# Board.net
KiCad netlist of a schematic drawn in EAGLE
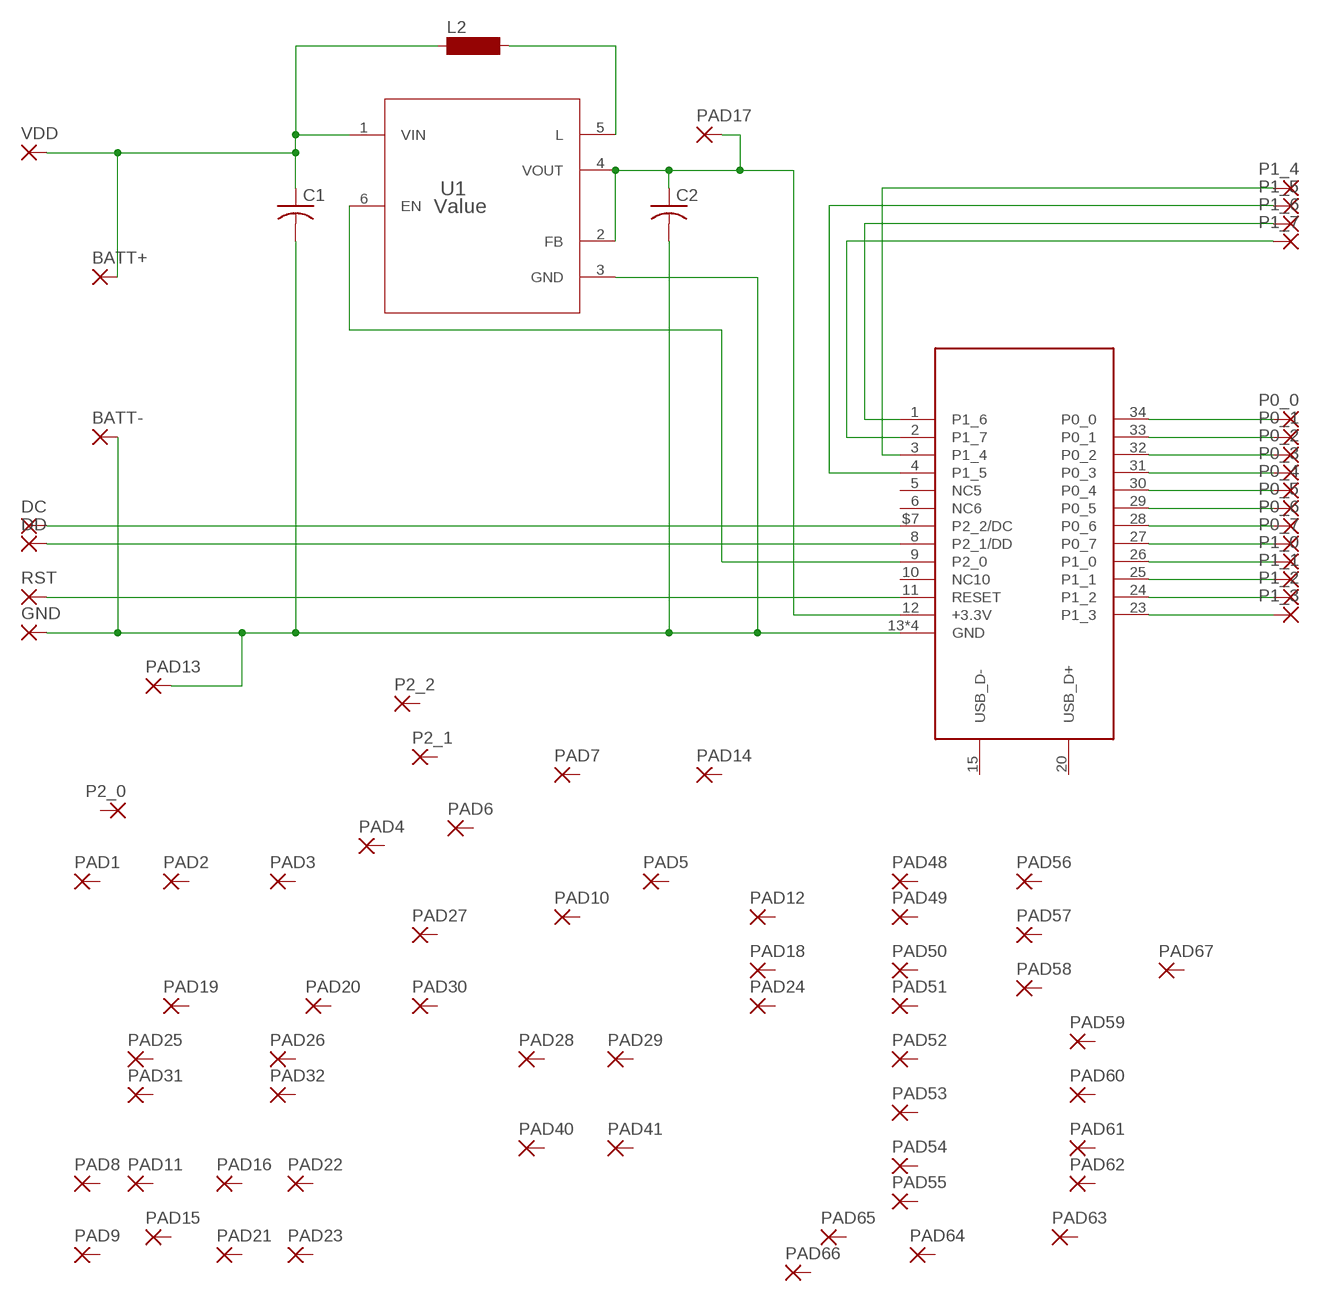
[diagram p0: schematic, sheet 1]

(export (version "E")
  (design (tool "Eeschema 10.0.6"))
  (components
    (comp (ref "BATT+")
      (value "1,6/0,9")
      (footprint "eagle-import:1,6_0,9")
      (libsource (lib "eagle-import") (part "1,6/0,9"))
    )
    (comp (ref "BATT-")
      (value "1,6/0,9")
      (footprint "eagle-import:1,6_0,9")
      (libsource (lib "eagle-import") (part "1,6/0,9"))
    )
    (comp (ref "C1")
      (value "C-USC0402")
      (footprint "eagle-import:C0402")
      (libsource (lib "eagle-import") (part "C-USC0402"))
    )
    (comp (ref "C2")
      (value "C-USC0402")
      (footprint "eagle-import:C0402")
      (libsource (lib "eagle-import") (part "C-USC0402"))
    )
    (comp (ref "DC")
      (value "SMD2")
      (footprint "eagle-import:SMD1,27-2,54")
      (libsource (lib "eagle-import") (part "SMD2"))
    )
    (comp (ref "DD")
      (value "SMD2")
      (footprint "eagle-import:SMD1,27-2,54")
      (libsource (lib "eagle-import") (part "SMD2"))
    )
    (comp (ref "E1")
      (value "HM-10-BOARD")
      (footprint "eagle-import:26.9X13X2.2_BOARD")
      (libsource (lib "eagle-import") (part "HM-10-BOARD"))
    )
    (comp (ref "GND")
      (value "SMD2")
      (footprint "eagle-import:SMD1,27-2,54")
      (libsource (lib "eagle-import") (part "SMD2"))
    )
    (comp (ref "L2")
      (value "SM-NE29")
      (footprint "eagle-import:SM-NE29")
      (libsource (lib "eagle-import") (part "SM-NE29"))
    )
    (comp (ref "P0_0")
      (value "1,6/0,9")
      (footprint "eagle-import:1,6_0,9")
      (libsource (lib "eagle-import") (part "1,6/0,9"))
    )
    (comp (ref "P0_1")
      (value "1,6/0,9")
      (footprint "eagle-import:1,6_0,9")
      (libsource (lib "eagle-import") (part "1,6/0,9"))
    )
    (comp (ref "P0_2")
      (value "1,6/0,9")
      (footprint "eagle-import:1,6_0,9")
      (libsource (lib "eagle-import") (part "1,6/0,9"))
    )
    (comp (ref "P0_3")
      (value "1,6/0,9")
      (footprint "eagle-import:1,6_0,9")
      (libsource (lib "eagle-import") (part "1,6/0,9"))
    )
    (comp (ref "P0_4")
      (value "1,6/0,9")
      (footprint "eagle-import:1,6_0,9")
      (libsource (lib "eagle-import") (part "1,6/0,9"))
    )
    (comp (ref "P0_5")
      (value "1,6/0,9")
      (footprint "eagle-import:1,6_0,9")
      (libsource (lib "eagle-import") (part "1,6/0,9"))
    )
    (comp (ref "P0_6")
      (value "1,6/0,9")
      (footprint "eagle-import:1,6_0,9")
      (libsource (lib "eagle-import") (part "1,6/0,9"))
    )
    (comp (ref "P0_7")
      (value "1,6/0,9")
      (footprint "eagle-import:1,6_0,9")
      (libsource (lib "eagle-import") (part "1,6/0,9"))
    )
    (comp (ref "P1_0")
      (value "1,6/0,9")
      (footprint "eagle-import:1,6_0,9")
      (libsource (lib "eagle-import") (part "1,6/0,9"))
    )
    (comp (ref "P1_1")
      (value "1,6/0,9")
      (footprint "eagle-import:1,6_0,9")
      (libsource (lib "eagle-import") (part "1,6/0,9"))
    )
    (comp (ref "P1_2")
      (value "1,6/0,9")
      (footprint "eagle-import:1,6_0,9")
      (libsource (lib "eagle-import") (part "1,6/0,9"))
    )
    (comp (ref "P1_3")
      (value "1,6/0,9")
      (footprint "eagle-import:1,6_0,9")
      (libsource (lib "eagle-import") (part "1,6/0,9"))
    )
    (comp (ref "P1_4")
      (value "1,6/0,9")
      (footprint "eagle-import:1,6_0,9")
      (libsource (lib "eagle-import") (part "1,6/0,9"))
    )
    (comp (ref "P1_5")
      (value "1,6/0,9")
      (footprint "eagle-import:1,6_0,9")
      (libsource (lib "eagle-import") (part "1,6/0,9"))
    )
    (comp (ref "P1_6")
      (value "1,6/0,9")
      (footprint "eagle-import:1,6_0,9")
      (libsource (lib "eagle-import") (part "1,6/0,9"))
    )
    (comp (ref "P1_7")
      (value "1,6/0,9")
      (footprint "eagle-import:1,6_0,9")
      (libsource (lib "eagle-import") (part "1,6/0,9"))
    )
    (comp (ref "P2_0")
      (value "1,6/0,9")
      (footprint "eagle-import:1,6_0,9")
      (libsource (lib "eagle-import") (part "1,6/0,9"))
    )
    (comp (ref "P2_1")
      (value "1,6/0,9")
      (footprint "eagle-import:1,6_0,9")
      (libsource (lib "eagle-import") (part "1,6/0,9"))
    )
    (comp (ref "P2_2")
      (value "1,6/0,9")
      (footprint "eagle-import:1,6_0,9")
      (libsource (lib "eagle-import") (part "1,6/0,9"))
    )
    (comp (ref "PAD1")
      (value "1,6/0,9")
      (footprint "eagle-import:1,6_0,9")
      (libsource (lib "eagle-import") (part "1,6/0,9"))
    )
    (comp (ref "PAD2")
      (value "1,6/0,9")
      (footprint "eagle-import:1,6_0,9")
      (libsource (lib "eagle-import") (part "1,6/0,9"))
    )
    (comp (ref "PAD3")
      (value "1,6/0,9")
      (footprint "eagle-import:1,6_0,9")
      (libsource (lib "eagle-import") (part "1,6/0,9"))
    )
    (comp (ref "PAD4")
      (value "1,6/0,9")
      (footprint "eagle-import:1,6_0,9")
      (libsource (lib "eagle-import") (part "1,6/0,9"))
    )
    (comp (ref "PAD5")
      (value "1,6/0,9")
      (footprint "eagle-import:1,6_0,9")
      (libsource (lib "eagle-import") (part "1,6/0,9"))
    )
    (comp (ref "PAD6")
      (value "1,6/0,9")
      (footprint "eagle-import:1,6_0,9")
      (libsource (lib "eagle-import") (part "1,6/0,9"))
    )
    (comp (ref "PAD7")
      (value "1,6/0,9")
      (footprint "eagle-import:1,6_0,9")
      (libsource (lib "eagle-import") (part "1,6/0,9"))
    )
    (comp (ref "PAD8")
      (value "1,6/0,9")
      (footprint "eagle-import:1,6_0,9")
      (libsource (lib "eagle-import") (part "1,6/0,9"))
    )
    (comp (ref "PAD9")
      (value "1,6/0,9")
      (footprint "eagle-import:1,6_0,9")
      (libsource (lib "eagle-import") (part "1,6/0,9"))
    )
    (comp (ref "PAD10")
      (value "1,6/0,9")
      (footprint "eagle-import:1,6_0,9")
      (libsource (lib "eagle-import") (part "1,6/0,9"))
    )
    (comp (ref "PAD11")
      (value "1,6/0,9")
      (footprint "eagle-import:1,6_0,9")
      (libsource (lib "eagle-import") (part "1,6/0,9"))
    )
    (comp (ref "PAD12")
      (value "1,6/0,9")
      (footprint "eagle-import:1,6_0,9")
      (libsource (lib "eagle-import") (part "1,6/0,9"))
    )
    (comp (ref "PAD13")
      (value "1,6/0,9")
      (footprint "eagle-import:1,6_0,9")
      (libsource (lib "eagle-import") (part "1,6/0,9"))
    )
    (comp (ref "PAD14")
      (value "1,6/0,9")
      (footprint "eagle-import:1,6_0,9")
      (libsource (lib "eagle-import") (part "1,6/0,9"))
    )
    (comp (ref "PAD15")
      (value "1,6/0,9")
      (footprint "eagle-import:1,6_0,9")
      (libsource (lib "eagle-import") (part "1,6/0,9"))
    )
    (comp (ref "PAD16")
      (value "1,6/0,9")
      (footprint "eagle-import:1,6_0,9")
      (libsource (lib "eagle-import") (part "1,6/0,9"))
    )
    (comp (ref "PAD17")
      (value "1,6/0,9")
      (footprint "eagle-import:1,6_0,9")
      (libsource (lib "eagle-import") (part "1,6/0,9"))
    )
    (comp (ref "PAD18")
      (value "1,6/0,9")
      (footprint "eagle-import:1,6_0,9")
      (libsource (lib "eagle-import") (part "1,6/0,9"))
    )
    (comp (ref "PAD19")
      (value "1,6/0,9")
      (footprint "eagle-import:1,6_0,9")
      (libsource (lib "eagle-import") (part "1,6/0,9"))
    )
    (comp (ref "PAD20")
      (value "1,6/0,9")
      (footprint "eagle-import:1,6_0,9")
      (libsource (lib "eagle-import") (part "1,6/0,9"))
    )
    (comp (ref "PAD21")
      (value "1,6/0,9")
      (footprint "eagle-import:1,6_0,9")
      (libsource (lib "eagle-import") (part "1,6/0,9"))
    )
    (comp (ref "PAD22")
      (value "1,6/0,9")
      (footprint "eagle-import:1,6_0,9")
      (libsource (lib "eagle-import") (part "1,6/0,9"))
    )
    (comp (ref "PAD23")
      (value "1,6/0,9")
      (footprint "eagle-import:1,6_0,9")
      (libsource (lib "eagle-import") (part "1,6/0,9"))
    )
    (comp (ref "PAD24")
      (value "1,6/0,9")
      (footprint "eagle-import:1,6_0,9")
      (libsource (lib "eagle-import") (part "1,6/0,9"))
    )
    (comp (ref "PAD25")
      (value "1,6/0,9")
      (footprint "eagle-import:1,6_0,9")
      (libsource (lib "eagle-import") (part "1,6/0,9"))
    )
    (comp (ref "PAD26")
      (value "1,6/0,9")
      (footprint "eagle-import:1,6_0,9")
      (libsource (lib "eagle-import") (part "1,6/0,9"))
    )
    (comp (ref "PAD27")
      (value "1,6/0,9")
      (footprint "eagle-import:1,6_0,9")
      (libsource (lib "eagle-import") (part "1,6/0,9"))
    )
    (comp (ref "PAD28")
      (value "1,6/0,9")
      (footprint "eagle-import:1,6_0,9")
      (libsource (lib "eagle-import") (part "1,6/0,9"))
    )
    (comp (ref "PAD29")
      (value "1,6/0,9")
      (footprint "eagle-import:1,6_0,9")
      (libsource (lib "eagle-import") (part "1,6/0,9"))
    )
    (comp (ref "PAD30")
      (value "1,6/0,9")
      (footprint "eagle-import:1,6_0,9")
      (libsource (lib "eagle-import") (part "1,6/0,9"))
    )
    (comp (ref "PAD31")
      (value "1,6/0,9")
      (footprint "eagle-import:1,6_0,9")
      (libsource (lib "eagle-import") (part "1,6/0,9"))
    )
    (comp (ref "PAD32")
      (value "1,6/0,9")
      (footprint "eagle-import:1,6_0,9")
      (libsource (lib "eagle-import") (part "1,6/0,9"))
    )
    (comp (ref "PAD40")
      (value "1,6/0,9")
      (footprint "eagle-import:1,6_0,9")
      (libsource (lib "eagle-import") (part "1,6/0,9"))
    )
    (comp (ref "PAD41")
      (value "1,6/0,9")
      (footprint "eagle-import:1,6_0,9")
      (libsource (lib "eagle-import") (part "1,6/0,9"))
    )
    (comp (ref "PAD48")
      (value "1,6/0,9")
      (footprint "eagle-import:1,6_0,9")
      (libsource (lib "eagle-import") (part "1,6/0,9"))
    )
    (comp (ref "PAD49")
      (value "1,6/0,9")
      (footprint "eagle-import:1,6_0,9")
      (libsource (lib "eagle-import") (part "1,6/0,9"))
    )
    (comp (ref "PAD50")
      (value "1,6/0,9")
      (footprint "eagle-import:1,6_0,9")
      (libsource (lib "eagle-import") (part "1,6/0,9"))
    )
    (comp (ref "PAD51")
      (value "1,6/0,9")
      (footprint "eagle-import:1,6_0,9")
      (libsource (lib "eagle-import") (part "1,6/0,9"))
    )
    (comp (ref "PAD52")
      (value "1,6/0,9")
      (footprint "eagle-import:1,6_0,9")
      (libsource (lib "eagle-import") (part "1,6/0,9"))
    )
    (comp (ref "PAD53")
      (value "1,6/0,9")
      (footprint "eagle-import:1,6_0,9")
      (libsource (lib "eagle-import") (part "1,6/0,9"))
    )
    (comp (ref "PAD54")
      (value "1,6/0,9")
      (footprint "eagle-import:1,6_0,9")
      (libsource (lib "eagle-import") (part "1,6/0,9"))
    )
    (comp (ref "PAD55")
      (value "1,6/0,9")
      (footprint "eagle-import:1,6_0,9")
      (libsource (lib "eagle-import") (part "1,6/0,9"))
    )
    (comp (ref "PAD56")
      (value "1,6/0,9")
      (footprint "eagle-import:1,6_0,9")
      (libsource (lib "eagle-import") (part "1,6/0,9"))
    )
    (comp (ref "PAD57")
      (value "1,6/0,9")
      (footprint "eagle-import:1,6_0,9")
      (libsource (lib "eagle-import") (part "1,6/0,9"))
    )
    (comp (ref "PAD58")
      (value "1,6/0,9")
      (footprint "eagle-import:1,6_0,9")
      (libsource (lib "eagle-import") (part "1,6/0,9"))
    )
    (comp (ref "PAD59")
      (value "1,6/0,9")
      (footprint "eagle-import:1,6_0,9")
      (libsource (lib "eagle-import") (part "1,6/0,9"))
    )
    (comp (ref "PAD60")
      (value "1,6/0,9")
      (footprint "eagle-import:1,6_0,9")
      (libsource (lib "eagle-import") (part "1,6/0,9"))
    )
    (comp (ref "PAD61")
      (value "1,6/0,9")
      (footprint "eagle-import:1,6_0,9")
      (libsource (lib "eagle-import") (part "1,6/0,9"))
    )
    (comp (ref "PAD62")
      (value "1,6/0,9")
      (footprint "eagle-import:1,6_0,9")
      (libsource (lib "eagle-import") (part "1,6/0,9"))
    )
    (comp (ref "PAD63")
      (value "1,6/0,9")
      (footprint "eagle-import:1,6_0,9")
      (libsource (lib "eagle-import") (part "1,6/0,9"))
    )
    (comp (ref "PAD64")
      (value "1,6/0,9")
      (footprint "eagle-import:1,6_0,9")
      (libsource (lib "eagle-import") (part "1,6/0,9"))
    )
    (comp (ref "PAD65")
      (value "1,6/0,9")
      (footprint "eagle-import:1,6_0,9")
      (libsource (lib "eagle-import") (part "1,6/0,9"))
    )
    (comp (ref "PAD66")
      (value "1,6/0,9")
      (footprint "eagle-import:1,6_0,9")
      (libsource (lib "eagle-import") (part "1,6/0,9"))
    )
    (comp (ref "PAD67")
      (value "1,6/0,9")
      (footprint "eagle-import:1,6_0,9")
      (libsource (lib "eagle-import") (part "1,6/0,9"))
    )
    (comp (ref "RST")
      (value "SMD2")
      (footprint "eagle-import:SMD1,27-2,54")
      (libsource (lib "eagle-import") (part "SMD2"))
    )
    (comp (ref "U1")
      (value "Value")
      (footprint "eagle-import:DCK0006A")
      (fields (field (name "MANUFACTURER") "Texas Instruments") (field (name "PARTNUMBER") "TPS61221DCK"))
      (libsource (lib "eagle-import") (part "TPS61221DCKR"))
    )
    (comp (ref "VDD")
      (value "SMD2")
      (footprint "eagle-import:SMD1,27-2,54")
      (libsource (lib "eagle-import") (part "SMD2"))
    )
  )
  (nets
    (net (code "1") (name "Net-(BATT+-P)") (class "Default")
      (node (ref "BATT+") (pin "1") (pinfunction "P_1") (pintype "passive"))
      (node (ref "C1") (pin "1") (pinfunction "1_1") (pintype "passive"))
      (node (ref "L2") (pin "1") (pinfunction "1_1") (pintype "passive"))
      (node (ref "U1") (pin "1") (pinfunction "VIN_1") (pintype "power_in"))
      (node (ref "VDD") (pin "1") (pinfunction "P_1") (pintype "passive"))
    )
    (net (code "2") (name "Net-(BATT--P)") (class "Default")
      (node (ref "BATT-") (pin "1") (pinfunction "P_1") (pintype "passive"))
      (node (ref "C1") (pin "2") (pinfunction "2_2") (pintype "passive"))
      (node (ref "C2") (pin "2") (pinfunction "2_2") (pintype "passive"))
      (node (ref "E1") (pin "13") (pinfunction "GND_13") (pintype "bidirectional"))
      (node (ref "E1") (pin "14") (pinfunction "GND_14") (pintype "bidirectional"))
      (node (ref "E1") (pin "21") (pinfunction "GND_21") (pintype "bidirectional"))
      (node (ref "E1") (pin "22") (pinfunction "GND_22") (pintype "bidirectional"))
      (node (ref "GND") (pin "1") (pinfunction "P_1") (pintype "passive"))
      (node (ref "PAD13") (pin "1") (pinfunction "P_1") (pintype "passive"))
      (node (ref "U1") (pin "3") (pinfunction "GND_3") (pintype "power_in"))
    )
    (net (code "3") (name "Net-(DC-P)") (class "Default")
      (node (ref "DC") (pin "1") (pinfunction "P_1") (pintype "passive"))
      (node (ref "E1") (pin "$7") (pinfunction "P2_2/DC_$7") (pintype "bidirectional"))
    )
    (net (code "4") (name "Net-(DD-P)") (class "Default")
      (node (ref "DD") (pin "1") (pinfunction "P_1") (pintype "passive"))
      (node (ref "E1") (pin "8") (pinfunction "P2_1/DD_8") (pintype "bidirectional"))
    )
    (net (code "5") (name "Net-(E1-+3.3V)") (class "Default")
      (node (ref "C2") (pin "1") (pinfunction "1_1") (pintype "passive"))
      (node (ref "E1") (pin "12") (pinfunction "+3.3V_12") (pintype "bidirectional"))
      (node (ref "PAD17") (pin "1") (pinfunction "P_1") (pintype "passive"))
      (node (ref "U1") (pin "2") (pinfunction "FB_2") (pintype "input"))
      (node (ref "U1") (pin "4") (pinfunction "VOUT_4") (pintype "power_in"))
    )
    (net (code "6") (name "Net-(E1-P0_0)") (class "Default")
      (node (ref "E1") (pin "34") (pinfunction "P0_0_34") (pintype "bidirectional"))
      (node (ref "P0_0") (pin "1") (pinfunction "P_1") (pintype "passive"))
    )
    (net (code "7") (name "Net-(E1-P0_1)") (class "Default")
      (node (ref "E1") (pin "33") (pinfunction "P0_1_33") (pintype "bidirectional"))
      (node (ref "P0_1") (pin "1") (pinfunction "P_1") (pintype "passive"))
    )
    (net (code "8") (name "Net-(E1-P0_2)") (class "Default")
      (node (ref "E1") (pin "32") (pinfunction "P0_2_32") (pintype "bidirectional"))
      (node (ref "P0_2") (pin "1") (pinfunction "P_1") (pintype "passive"))
    )
    (net (code "9") (name "Net-(E1-P0_3)") (class "Default")
      (node (ref "E1") (pin "31") (pinfunction "P0_3_31") (pintype "bidirectional"))
      (node (ref "P0_3") (pin "1") (pinfunction "P_1") (pintype "passive"))
    )
    (net (code "10") (name "Net-(E1-P0_4)") (class "Default")
      (node (ref "E1") (pin "30") (pinfunction "P0_4_30") (pintype "bidirectional"))
      (node (ref "P0_4") (pin "1") (pinfunction "P_1") (pintype "passive"))
    )
    (net (code "11") (name "Net-(E1-P0_5)") (class "Default")
      (node (ref "E1") (pin "29") (pinfunction "P0_5_29") (pintype "bidirectional"))
      (node (ref "P0_5") (pin "1") (pinfunction "P_1") (pintype "passive"))
    )
    (net (code "12") (name "Net-(E1-P0_6)") (class "Default")
      (node (ref "E1") (pin "28") (pinfunction "P0_6_28") (pintype "bidirectional"))
      (node (ref "P0_6") (pin "1") (pinfunction "P_1") (pintype "passive"))
    )
    (net (code "13") (name "Net-(E1-P0_7)") (class "Default")
      (node (ref "E1") (pin "27") (pinfunction "P0_7_27") (pintype "bidirectional"))
      (node (ref "P0_7") (pin "1") (pinfunction "P_1") (pintype "passive"))
    )
    (net (code "14") (name "Net-(E1-P1_0)") (class "Default")
      (node (ref "E1") (pin "26") (pinfunction "P1_0_26") (pintype "bidirectional"))
      (node (ref "P1_0") (pin "1") (pinfunction "P_1") (pintype "passive"))
    )
    (net (code "15") (name "Net-(E1-P1_1)") (class "Default")
      (node (ref "E1") (pin "25") (pinfunction "P1_1_25") (pintype "bidirectional"))
      (node (ref "P1_1") (pin "1") (pinfunction "P_1") (pintype "passive"))
    )
    (net (code "16") (name "Net-(E1-P1_2)") (class "Default")
      (node (ref "E1") (pin "24") (pinfunction "P1_2_24") (pintype "bidirectional"))
      (node (ref "P1_2") (pin "1") (pinfunction "P_1") (pintype "passive"))
    )
    (net (code "17") (name "Net-(E1-P1_3)") (class "Default")
      (node (ref "E1") (pin "23") (pinfunction "P1_3_23") (pintype "bidirectional"))
      (node (ref "P1_3") (pin "1") (pinfunction "P_1") (pintype "passive"))
    )
    (net (code "18") (name "Net-(E1-P1_4)") (class "Default")
      (node (ref "E1") (pin "3") (pinfunction "P1_4_3") (pintype "bidirectional"))
      (node (ref "P1_4") (pin "1") (pinfunction "P_1") (pintype "passive"))
    )
    (net (code "19") (name "Net-(E1-P1_5)") (class "Default")
      (node (ref "E1") (pin "4") (pinfunction "P1_5_4") (pintype "bidirectional"))
      (node (ref "P1_5") (pin "1") (pinfunction "P_1") (pintype "passive"))
    )
    (net (code "20") (name "Net-(E1-P1_6)") (class "Default")
      (node (ref "E1") (pin "1") (pinfunction "P1_6_1") (pintype "bidirectional"))
      (node (ref "P1_6") (pin "1") (pinfunction "P_1") (pintype "passive"))
    )
    (net (code "21") (name "Net-(E1-P1_7)") (class "Default")
      (node (ref "E1") (pin "2") (pinfunction "P1_7_2") (pintype "bidirectional"))
      (node (ref "P1_7") (pin "1") (pinfunction "P_1") (pintype "passive"))
    )
    (net (code "22") (name "Net-(E1-P2_0)") (class "Default")
      (node (ref "E1") (pin "9") (pinfunction "P2_0_9") (pintype "bidirectional"))
      (node (ref "U1") (pin "6") (pinfunction "EN_6") (pintype "input"))
    )
    (net (code "23") (name "Net-(E1-RESET)") (class "Default")
      (node (ref "E1") (pin "11") (pinfunction "RESET_11") (pintype "bidirectional"))
      (node (ref "RST") (pin "1") (pinfunction "P_1") (pintype "passive"))
    )
    (net (code "24") (name "Net-(U1-L)") (class "Default")
      (node (ref "L2") (pin "2") (pinfunction "2_2") (pintype "passive"))
      (node (ref "U1") (pin "5") (pinfunction "L_5") (pintype "passive"))
    )
    (net (code "25") (name "unconnected-(E1-NC5-Pad5)") (class "Default")
      (node (ref "E1") (pin "5") (pinfunction "NC5_5") (pintype "bidirectional"))
    )
    (net (code "26") (name "unconnected-(E1-NC6-Pad6)") (class "Default")
      (node (ref "E1") (pin "6") (pinfunction "NC6_6") (pintype "bidirectional"))
    )
    (net (code "27") (name "unconnected-(E1-NC10-Pad10)") (class "Default")
      (node (ref "E1") (pin "10") (pinfunction "NC10_10") (pintype "bidirectional"))
    )
    (net (code "28") (name "unconnected-(E1-USB_D+-Pad20)") (class "Default")
      (node (ref "E1") (pin "20") (pinfunction "USB_D+_20") (pintype "bidirectional"))
    )
    (net (code "29") (name "unconnected-(E1-USB_D--Pad15)") (class "Default")
      (node (ref "E1") (pin "15") (pinfunction "USB_D-_15") (pintype "bidirectional"))
    )
    (net (code "30") (name "unconnected-(P2_0-P-Pad1)") (class "Default")
      (node (ref "P2_0") (pin "1") (pinfunction "P_1") (pintype "passive"))
    )
    (net (code "31") (name "unconnected-(P2_1-P-Pad1)") (class "Default")
      (node (ref "P2_1") (pin "1") (pinfunction "P_1") (pintype "passive"))
    )
    (net (code "32") (name "unconnected-(P2_2-P-Pad1)") (class "Default")
      (node (ref "P2_2") (pin "1") (pinfunction "P_1") (pintype "passive"))
    )
    (net (code "33") (name "unconnected-(PAD1-P-Pad1)") (class "Default")
      (node (ref "PAD1") (pin "1") (pinfunction "P_1") (pintype "passive"))
    )
    (net (code "34") (name "unconnected-(PAD2-P-Pad1)") (class "Default")
      (node (ref "PAD2") (pin "1") (pinfunction "P_1") (pintype "passive"))
    )
    (net (code "35") (name "unconnected-(PAD3-P-Pad1)") (class "Default")
      (node (ref "PAD3") (pin "1") (pinfunction "P_1") (pintype "passive"))
    )
    (net (code "36") (name "unconnected-(PAD4-P-Pad1)") (class "Default")
      (node (ref "PAD4") (pin "1") (pinfunction "P_1") (pintype "passive"))
    )
    (net (code "37") (name "unconnected-(PAD5-P-Pad1)") (class "Default")
      (node (ref "PAD5") (pin "1") (pinfunction "P_1") (pintype "passive"))
    )
    (net (code "38") (name "unconnected-(PAD6-P-Pad1)") (class "Default")
      (node (ref "PAD6") (pin "1") (pinfunction "P_1") (pintype "passive"))
    )
    (net (code "39") (name "unconnected-(PAD7-P-Pad1)") (class "Default")
      (node (ref "PAD7") (pin "1") (pinfunction "P_1") (pintype "passive"))
    )
    (net (code "40") (name "unconnected-(PAD8-P-Pad1)") (class "Default")
      (node (ref "PAD8") (pin "1") (pinfunction "P_1") (pintype "passive"))
    )
    (net (code "41") (name "unconnected-(PAD9-P-Pad1)") (class "Default")
      (node (ref "PAD9") (pin "1") (pinfunction "P_1") (pintype "passive"))
    )
    (net (code "42") (name "unconnected-(PAD10-P-Pad1)") (class "Default")
      (node (ref "PAD10") (pin "1") (pinfunction "P_1") (pintype "passive"))
    )
    (net (code "43") (name "unconnected-(PAD11-P-Pad1)") (class "Default")
      (node (ref "PAD11") (pin "1") (pinfunction "P_1") (pintype "passive"))
    )
    (net (code "44") (name "unconnected-(PAD12-P-Pad1)") (class "Default")
      (node (ref "PAD12") (pin "1") (pinfunction "P_1") (pintype "passive"))
    )
    (net (code "45") (name "unconnected-(PAD14-P-Pad1)") (class "Default")
      (node (ref "PAD14") (pin "1") (pinfunction "P_1") (pintype "passive"))
    )
    (net (code "46") (name "unconnected-(PAD15-P-Pad1)") (class "Default")
      (node (ref "PAD15") (pin "1") (pinfunction "P_1") (pintype "passive"))
    )
    (net (code "47") (name "unconnected-(PAD16-P-Pad1)") (class "Default")
      (node (ref "PAD16") (pin "1") (pinfunction "P_1") (pintype "passive"))
    )
    (net (code "48") (name "unconnected-(PAD18-P-Pad1)") (class "Default")
      (node (ref "PAD18") (pin "1") (pinfunction "P_1") (pintype "passive"))
    )
    (net (code "49") (name "unconnected-(PAD19-P-Pad1)") (class "Default")
      (node (ref "PAD19") (pin "1") (pinfunction "P_1") (pintype "passive"))
    )
    (net (code "50") (name "unconnected-(PAD20-P-Pad1)") (class "Default")
      (node (ref "PAD20") (pin "1") (pinfunction "P_1") (pintype "passive"))
    )
    (net (code "51") (name "unconnected-(PAD21-P-Pad1)") (class "Default")
      (node (ref "PAD21") (pin "1") (pinfunction "P_1") (pintype "passive"))
    )
    (net (code "52") (name "unconnected-(PAD22-P-Pad1)") (class "Default")
      (node (ref "PAD22") (pin "1") (pinfunction "P_1") (pintype "passive"))
    )
    (net (code "53") (name "unconnected-(PAD23-P-Pad1)") (class "Default")
      (node (ref "PAD23") (pin "1") (pinfunction "P_1") (pintype "passive"))
    )
    (net (code "54") (name "unconnected-(PAD24-P-Pad1)") (class "Default")
      (node (ref "PAD24") (pin "1") (pinfunction "P_1") (pintype "passive"))
    )
    (net (code "55") (name "unconnected-(PAD25-P-Pad1)") (class "Default")
      (node (ref "PAD25") (pin "1") (pinfunction "P_1") (pintype "passive"))
    )
    (net (code "56") (name "unconnected-(PAD26-P-Pad1)") (class "Default")
      (node (ref "PAD26") (pin "1") (pinfunction "P_1") (pintype "passive"))
    )
    (net (code "57") (name "unconnected-(PAD27-P-Pad1)") (class "Default")
      (node (ref "PAD27") (pin "1") (pinfunction "P_1") (pintype "passive"))
    )
    (net (code "58") (name "unconnected-(PAD28-P-Pad1)") (class "Default")
      (node (ref "PAD28") (pin "1") (pinfunction "P_1") (pintype "passive"))
    )
    (net (code "59") (name "unconnected-(PAD29-P-Pad1)") (class "Default")
      (node (ref "PAD29") (pin "1") (pinfunction "P_1") (pintype "passive"))
    )
    (net (code "60") (name "unconnected-(PAD30-P-Pad1)") (class "Default")
      (node (ref "PAD30") (pin "1") (pinfunction "P_1") (pintype "passive"))
    )
    (net (code "61") (name "unconnected-(PAD31-P-Pad1)") (class "Default")
      (node (ref "PAD31") (pin "1") (pinfunction "P_1") (pintype "passive"))
    )
    (net (code "62") (name "unconnected-(PAD32-P-Pad1)") (class "Default")
      (node (ref "PAD32") (pin "1") (pinfunction "P_1") (pintype "passive"))
    )
    (net (code "63") (name "unconnected-(PAD40-P-Pad1)") (class "Default")
      (node (ref "PAD40") (pin "1") (pinfunction "P_1") (pintype "passive"))
    )
    (net (code "64") (name "unconnected-(PAD41-P-Pad1)") (class "Default")
      (node (ref "PAD41") (pin "1") (pinfunction "P_1") (pintype "passive"))
    )
    (net (code "65") (name "unconnected-(PAD48-P-Pad1)") (class "Default")
      (node (ref "PAD48") (pin "1") (pinfunction "P_1") (pintype "passive"))
    )
    (net (code "66") (name "unconnected-(PAD49-P-Pad1)") (class "Default")
      (node (ref "PAD49") (pin "1") (pinfunction "P_1") (pintype "passive"))
    )
    (net (code "67") (name "unconnected-(PAD50-P-Pad1)") (class "Default")
      (node (ref "PAD50") (pin "1") (pinfunction "P_1") (pintype "passive"))
    )
    (net (code "68") (name "unconnected-(PAD51-P-Pad1)") (class "Default")
      (node (ref "PAD51") (pin "1") (pinfunction "P_1") (pintype "passive"))
    )
    (net (code "69") (name "unconnected-(PAD52-P-Pad1)") (class "Default")
      (node (ref "PAD52") (pin "1") (pinfunction "P_1") (pintype "passive"))
    )
    (net (code "70") (name "unconnected-(PAD53-P-Pad1)") (class "Default")
      (node (ref "PAD53") (pin "1") (pinfunction "P_1") (pintype "passive"))
    )
    (net (code "71") (name "unconnected-(PAD54-P-Pad1)") (class "Default")
      (node (ref "PAD54") (pin "1") (pinfunction "P_1") (pintype "passive"))
    )
    (net (code "72") (name "unconnected-(PAD55-P-Pad1)") (class "Default")
      (node (ref "PAD55") (pin "1") (pinfunction "P_1") (pintype "passive"))
    )
    (net (code "73") (name "unconnected-(PAD56-P-Pad1)") (class "Default")
      (node (ref "PAD56") (pin "1") (pinfunction "P_1") (pintype "passive"))
    )
    (net (code "74") (name "unconnected-(PAD57-P-Pad1)") (class "Default")
      (node (ref "PAD57") (pin "1") (pinfunction "P_1") (pintype "passive"))
    )
    (net (code "75") (name "unconnected-(PAD58-P-Pad1)") (class "Default")
      (node (ref "PAD58") (pin "1") (pinfunction "P_1") (pintype "passive"))
    )
    (net (code "76") (name "unconnected-(PAD59-P-Pad1)") (class "Default")
      (node (ref "PAD59") (pin "1") (pinfunction "P_1") (pintype "passive"))
    )
    (net (code "77") (name "unconnected-(PAD60-P-Pad1)") (class "Default")
      (node (ref "PAD60") (pin "1") (pinfunction "P_1") (pintype "passive"))
    )
    (net (code "78") (name "unconnected-(PAD61-P-Pad1)") (class "Default")
      (node (ref "PAD61") (pin "1") (pinfunction "P_1") (pintype "passive"))
    )
    (net (code "79") (name "unconnected-(PAD62-P-Pad1)") (class "Default")
      (node (ref "PAD62") (pin "1") (pinfunction "P_1") (pintype "passive"))
    )
    (net (code "80") (name "unconnected-(PAD63-P-Pad1)") (class "Default")
      (node (ref "PAD63") (pin "1") (pinfunction "P_1") (pintype "passive"))
    )
    (net (code "81") (name "unconnected-(PAD64-P-Pad1)") (class "Default")
      (node (ref "PAD64") (pin "1") (pinfunction "P_1") (pintype "passive"))
    )
    (net (code "82") (name "unconnected-(PAD65-P-Pad1)") (class "Default")
      (node (ref "PAD65") (pin "1") (pinfunction "P_1") (pintype "passive"))
    )
    (net (code "83") (name "unconnected-(PAD66-P-Pad1)") (class "Default")
      (node (ref "PAD66") (pin "1") (pinfunction "P_1") (pintype "passive"))
    )
    (net (code "84") (name "unconnected-(PAD67-P-Pad1)") (class "Default")
      (node (ref "PAD67") (pin "1") (pinfunction "P_1") (pintype "passive"))
    )
  )
)
